# MCU.net
KiCad netlist of a schematic drawn in Altium Designer
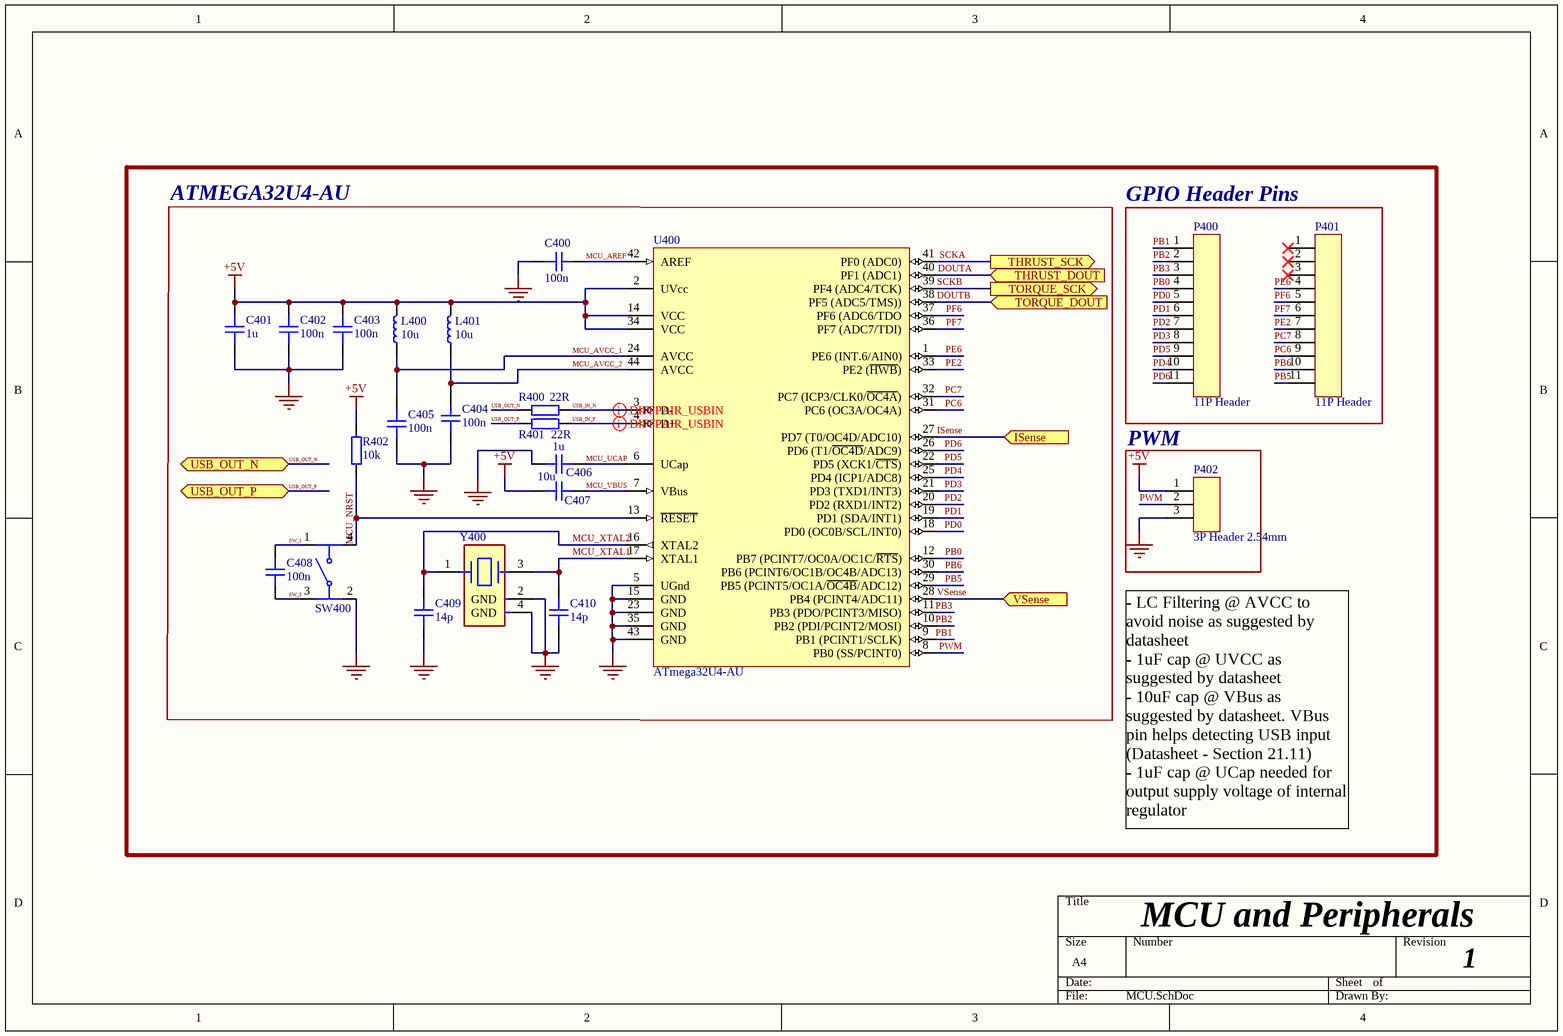
[diagram p0: MCU.SchDoc]

(export (version "E")
  (design (tool "Eeschema 10.0.6"))
  (components
    (comp (ref "C400")
      (value "100n")
      (footprint "CAP_0603")
      (description "Capacitor SMD 0603")
      (libsource (lib "Footprint-Lib-PhilsLab") (part "CAP_0603"))
    )
    (comp (ref "C401")
      (value "1u")
      (footprint "CAP_0603")
      (description "Capacitor SMD 0603")
      (libsource (lib "Footprint-Lib-PhilsLab") (part "CAP_0603"))
    )
    (comp (ref "C402")
      (value "100n")
      (footprint "CAP_0603")
      (description "Capacitor SMD 0603")
      (libsource (lib "Footprint-Lib-PhilsLab") (part "CAP_0603"))
    )
    (comp (ref "C403")
      (value "100n")
      (footprint "CAP_0603")
      (description "Capacitor SMD 0603")
      (libsource (lib "Footprint-Lib-PhilsLab") (part "CAP_0603"))
    )
    (comp (ref "C404")
      (value "100n")
      (footprint "CAP_0603")
      (description "Capacitor SMD 0603")
      (libsource (lib "Footprint-Lib-PhilsLab") (part "CAP_0603"))
    )
    (comp (ref "C405")
      (value "100n")
      (footprint "CAP_0603")
      (description "Capacitor SMD 0603")
      (libsource (lib "Footprint-Lib-PhilsLab") (part "CAP_0603"))
    )
    (comp (ref "C406")
      (value "1u")
      (footprint "CAP_0603")
      (description "Capacitor SMD 0603")
      (libsource (lib "Footprint-Lib-PhilsLab") (part "CAP_0603"))
    )
    (comp (ref "C407")
      (value "10u")
      (footprint "CAP_0603")
      (description "Capacitor SMD 0603")
      (libsource (lib "Footprint-Lib-PhilsLab") (part "CAP_0603"))
    )
    (comp (ref "C408")
      (value "100n")
      (footprint "CAP_0603")
      (description "Capacitor SMD 0603")
      (libsource (lib "Footprint-Lib-PhilsLab") (part "CAP_0603"))
    )
    (comp (ref "C409")
      (value "14p")
      (footprint "CAP_0603")
      (description "Capacitor SMD 0603")
      (libsource (lib "Footprint-Lib-PhilsLab") (part "CAP_0603"))
    )
    (comp (ref "C410")
      (value "14p")
      (footprint "CAP_0603")
      (description "Capacitor SMD 0603")
      (libsource (lib "Footprint-Lib-PhilsLab") (part "CAP_0603"))
    )
    (comp (ref "L400")
      (value "10u")
      (footprint "IND_0603")
      (description "Inductor SMD 0603")
      (libsource (lib "Footprint-Lib-PhilsLab") (part "IND_0603"))
    )
    (comp (ref "L401")
      (value "10u")
      (footprint "IND_0603")
      (description "Inductor SMD 0603")
      (libsource (lib "Footprint-Lib-PhilsLab") (part "IND_0603"))
    )
    (comp (ref "P400")
      (value "11P Header")
      (footprint "PZ254-1-11-Z-2.5-G1")
      (fields
        (field (name "MANUFACTURER") "HCTL")
        (field (name "MFR. PART NUMBER") "PZ254-1-11-Z-2.5-G1")
        (field (name "JLCPCB PART NUMBER") "C18197918")
      )
      (libsource (lib "Sidharth's Schematic Library") (part "PZ254-1-11-Z-2.5-G1"))
    )
    (comp (ref "P401")
      (value "11P Header")
      (footprint "PZ254-1-11-Z-2.5-G1")
      (fields
        (field (name "MANUFACTURER") "HCTL")
        (field (name "MFR. PART NUMBER") "PZ254-1-11-Z-2.5-G1")
        (field (name "JLCPCB PART NUMBER") "C18197918")
      )
      (libsource (lib "Sidharth's Schematic Library") (part "PZ254-1-11-Z-2.5-G1"))
    )
    (comp (ref "P402")
      (value "3P Header 2.54mm")
      (footprint "3P Header 2.54mm")
      (fields
        (field (name "MANUFACTURER") "XFCN")
        (field (name "MFR. PART #") "PZ254V-11-03P")
        (field (name "JLCPCB PART #") "C2937625")
      )
      (libsource (lib "Sidharth's Schematic Library") (part "PZ254V-11-03P"))
    )
    (comp (ref "R400")
      (value "22R")
      (footprint "RES_0603")
      (description "Resistor SMD 0603")
      (libsource (lib "Footprint-Lib-PhilsLab") (part "RES_0603"))
    )
    (comp (ref "R401")
      (value "22R")
      (footprint "RES_0603")
      (description "Resistor SMD 0603")
      (libsource (lib "Footprint-Lib-PhilsLab") (part "RES_0603"))
    )
    (comp (ref "R402")
      (value "10k")
      (footprint "RES_0603")
      (description "Resistor SMD 0603")
      (libsource (lib "Footprint-Lib-PhilsLab") (part "RES_0603"))
    )
    (comp (ref "SW400")
      (value "C318884")
      (footprint "C318884")
      (fields
        (field (name "MANUFACTURER") "XKB Connection")
        (field (name "MFR PART NUMBER") "TS-1187 A-B-A-B")
      )
      (libsource (lib "Sidharth's Schematic Library") (part "C318884"))
    )
    (comp (ref "U400")
      (value "ATmega32U4-AU")
      (footprint "44ML_M")
      (libsource (lib "Altium Content Vault") (part "MC-8B-ATM16U4-SQ44"))
    )
    (comp (ref "Y400")
      (value "7M-16.000MEEQ-T")
      (footprint "FP-7M-MFG")
      (description "Crystal 16MHz, 10ppm, 10pF, 60Ω")
      (fields (field (name "TOLERANCE") "10ppm"))
      (libsource (lib "Altium Content Vault") (part "41079aabb0e87794b56622915be14ed"))
    )
  )
  (nets
    (net (code "1") (name "+5V") (class "Default")
      (node (ref "C401") (pin "2") (pinfunction "2_2") (pintype "passive"))
      (node (ref "C402") (pin "2") (pinfunction "2_2") (pintype "passive"))
      (node (ref "C403") (pin "2") (pinfunction "2_2") (pintype "passive"))
      (node (ref "C407") (pin "2") (pinfunction "2_2") (pintype "passive"))
      (node (ref "L400") (pin "2") (pinfunction "2_2") (pintype "passive"))
      (node (ref "L401") (pin "2") (pinfunction "2_2") (pintype "passive"))
      (node (ref "P402") (pin "1") (pintype "passive"))
      (node (ref "R402") (pin "2") (pinfunction "2_2") (pintype "passive"))
      (node (ref "U400") (pin "14") (pinfunction "VCC_14") (pintype "power_in"))
      (node (ref "U400") (pin "2") (pinfunction "UVcc_2") (pintype "power_in"))
      (node (ref "U400") (pin "34") (pinfunction "VCC_34") (pintype "power_in"))
    )
    (net (code "2") (name "/DOUTA") (class "Default")
      (node (ref "U400") (pin "40") (pinfunction "PF1_(ADC1)_40") (pintype "bidirectional"))
    )
    (net (code "3") (name "/DOUTB") (class "Default")
      (node (ref "U400") (pin "38") (pinfunction "PF5_(ADC5/TMS))_38") (pintype "bidirectional"))
    )
    (net (code "4") (name "/ISense") (class "Default")
      (node (ref "U400") (pin "27") (pinfunction "PD7_(T0/OC4D/ADC10)_27") (pintype "bidirectional"))
    )
    (net (code "5") (name "/MCU_AREF") (class "Default")
      (node (ref "C400") (pin "1") (pinfunction "1_1") (pintype "passive"))
      (node (ref "U400") (pin "42") (pinfunction "AREF_42") (pintype "input"))
    )
    (net (code "6") (name "/MCU_AVCC_1") (class "Default")
      (node (ref "C405") (pin "2") (pinfunction "2_2") (pintype "passive"))
      (node (ref "L400") (pin "1") (pinfunction "1_1") (pintype "passive"))
      (node (ref "U400") (pin "24") (pinfunction "AVCC_24") (pintype "power_in"))
    )
    (net (code "7") (name "/MCU_AVCC_2") (class "Default")
      (node (ref "C404") (pin "2") (pinfunction "2_2") (pintype "passive"))
      (node (ref "L401") (pin "1") (pinfunction "1_1") (pintype "passive"))
      (node (ref "U400") (pin "44") (pinfunction "AVCC_44") (pintype "power_in"))
    )
    (net (code "8") (name "/MCU_NRST") (class "Default")
      (node (ref "R402") (pin "1") (pinfunction "1_1") (pintype "passive"))
      (node (ref "SW400") (pin "4") (pinfunction "4_4") (pintype "passive"))
      (node (ref "U400") (pin "13") (pinfunction "~{RESET}_13") (pintype "input"))
    )
    (net (code "9") (name "/MCU_UCAP") (class "Default")
      (node (ref "C406") (pin "1") (pinfunction "1_1") (pintype "passive"))
      (node (ref "U400") (pin "6") (pinfunction "UCap_6") (pintype "passive"))
    )
    (net (code "10") (name "/MCU_VBUS") (class "Default")
      (node (ref "C407") (pin "1") (pinfunction "1_1") (pintype "passive"))
      (node (ref "U400") (pin "7") (pinfunction "VBus_7") (pintype "input"))
    )
    (net (code "11") (name "/MCU_XTAL1") (class "Default")
      (node (ref "C410") (pin "2") (pinfunction "2_2") (pintype "passive"))
      (node (ref "U400") (pin "17") (pinfunction "XTAL1_17") (pintype "input"))
      (node (ref "Y400") (pin "3") (pinfunction "3_3") (pintype "passive"))
    )
    (net (code "12") (name "/MCU_XTAL2") (class "Default")
      (node (ref "C409") (pin "2") (pinfunction "2_2") (pintype "passive"))
      (node (ref "U400") (pin "16") (pinfunction "XTAL2_16") (pintype "output"))
      (node (ref "Y400") (pin "1") (pinfunction "1_1") (pintype "passive"))
    )
    (net (code "13") (name "/PB0") (class "Default")
      (node (ref "P400") (pin "4") (pintype "passive"))
      (node (ref "U400") (pin "12") (pinfunction "PB7_(PCINT7/OC0A/OC1C/~{RTS})_12") (pintype "bidirectional"))
    )
    (net (code "14") (name "/PB1") (class "Default")
      (node (ref "P400") (pin "1") (pintype "passive"))
      (node (ref "U400") (pin "9") (pinfunction "PB1_(PCINT1/SCLK)_9") (pintype "bidirectional"))
    )
    (net (code "15") (name "/PB2") (class "Default")
      (node (ref "P400") (pin "2") (pintype "passive"))
      (node (ref "U400") (pin "10") (pinfunction "PB2_(PDI/PCINT2/MOSI)_10") (pintype "bidirectional"))
    )
    (net (code "16") (name "/PB3") (class "Default")
      (node (ref "P400") (pin "3") (pintype "passive"))
      (node (ref "U400") (pin "11") (pinfunction "PB3_(PDO/PCINT3/MISO)_11") (pintype "bidirectional"))
    )
    (net (code "17") (name "/PB5") (class "Default")
      (node (ref "P401") (pin "11") (pintype "passive"))
      (node (ref "U400") (pin "29") (pinfunction "PB5_(PCINT5/OC1A/~{OC4B}/ADC12)_29") (pintype "bidirectional"))
    )
    (net (code "18") (name "/PB6") (class "Default")
      (node (ref "P401") (pin "10") (pintype "passive"))
      (node (ref "U400") (pin "30") (pinfunction "PB6_(PCINT6/OC1B/OC4B/ADC13)_30") (pintype "bidirectional"))
    )
    (net (code "19") (name "/PC6") (class "Default")
      (node (ref "P401") (pin "9") (pintype "passive"))
      (node (ref "U400") (pin "31") (pinfunction "PC6_(OC3A/OC4A)_31") (pintype "bidirectional"))
    )
    (net (code "20") (name "/PC7") (class "Default")
      (node (ref "P401") (pin "8") (pintype "passive"))
      (node (ref "U400") (pin "32") (pinfunction "PC7_(ICP3/CLK0/~{OC4A})_32") (pintype "bidirectional"))
    )
    (net (code "21") (name "/PD0") (class "Default")
      (node (ref "P400") (pin "5") (pintype "passive"))
      (node (ref "U400") (pin "18") (pinfunction "PD0_(OC0B/SCL/INT0)_18") (pintype "bidirectional"))
    )
    (net (code "22") (name "/PD1") (class "Default")
      (node (ref "P400") (pin "6") (pintype "passive"))
      (node (ref "U400") (pin "19") (pinfunction "PD1_(SDA/INT1)_19") (pintype "bidirectional"))
    )
    (net (code "23") (name "/PD2") (class "Default")
      (node (ref "P400") (pin "7") (pintype "passive"))
      (node (ref "U400") (pin "20") (pinfunction "PD2_(RXD1/INT2)_20") (pintype "bidirectional"))
    )
    (net (code "24") (name "/PD3") (class "Default")
      (node (ref "P400") (pin "8") (pintype "passive"))
      (node (ref "U400") (pin "21") (pinfunction "PD3_(TXD1/INT3)_21") (pintype "bidirectional"))
    )
    (net (code "25") (name "/PD4") (class "Default")
      (node (ref "P400") (pin "10") (pintype "passive"))
      (node (ref "U400") (pin "25") (pinfunction "PD4_(ICP1/ADC8)_25") (pintype "bidirectional"))
    )
    (net (code "26") (name "/PD5") (class "Default")
      (node (ref "P400") (pin "9") (pintype "passive"))
      (node (ref "U400") (pin "22") (pinfunction "PD5_(XCK1/~{CTS})_22") (pintype "bidirectional"))
    )
    (net (code "27") (name "/PD6") (class "Default")
      (node (ref "P400") (pin "11") (pintype "passive"))
      (node (ref "U400") (pin "26") (pinfunction "PD6_(T1/~{OC4D}/ADC9)_26") (pintype "bidirectional"))
    )
    (net (code "28") (name "/PE2") (class "Default")
      (node (ref "P401") (pin "7") (pintype "passive"))
      (node (ref "U400") (pin "33") (pinfunction "PE2_(~{HWB})_33") (pintype "bidirectional"))
    )
    (net (code "29") (name "/PE6") (class "Default")
      (node (ref "P401") (pin "4") (pintype "passive"))
      (node (ref "U400") (pin "1") (pinfunction "PE6_(INT.6/AIN0)_1") (pintype "bidirectional"))
    )
    (net (code "30") (name "/PF6") (class "Default")
      (node (ref "P401") (pin "5") (pintype "passive"))
      (node (ref "U400") (pin "37") (pinfunction "PF6_(ADC6/TDO_37") (pintype "bidirectional"))
    )
    (net (code "31") (name "/PF7") (class "Default")
      (node (ref "P401") (pin "6") (pintype "passive"))
      (node (ref "U400") (pin "36") (pinfunction "PF7_(ADC7/TDI)_36") (pintype "bidirectional"))
    )
    (net (code "32") (name "/PWM") (class "Default")
      (node (ref "P402") (pin "2") (pintype "passive"))
      (node (ref "U400") (pin "8") (pinfunction "PB0_(SS/PCINT0)_8") (pintype "bidirectional"))
    )
    (net (code "33") (name "/SCKA") (class "Default")
      (node (ref "U400") (pin "41") (pinfunction "PF0_(ADC0)_41") (pintype "bidirectional"))
    )
    (net (code "34") (name "/SCKB") (class "Default")
      (node (ref "U400") (pin "39") (pinfunction "PF4_(ADC4/TCK)_39") (pintype "bidirectional"))
    )
    (net (code "35") (name "/SW_1") (class "Default")
      (node (ref "C408") (pin "2") (pinfunction "2_2") (pintype "passive"))
      (node (ref "SW400") (pin "1") (pinfunction "1_1") (pintype "passive"))
    )
    (net (code "36") (name "/SW_3") (class "Default")
      (node (ref "C408") (pin "1") (pinfunction "1_1") (pintype "passive"))
      (node (ref "SW400") (pin "3") (pinfunction "3_3") (pintype "passive"))
    )
    (net (code "37") (name "/USB_IN_N") (class "Default")
      (node (ref "R400") (pin "2") (pinfunction "2_2") (pintype "passive"))
      (node (ref "U400") (pin "3") (pinfunction "D-_3") (pintype "bidirectional"))
    )
    (net (code "38") (name "/USB_IN_P") (class "Default")
      (node (ref "R401") (pin "2") (pinfunction "2_2") (pintype "passive"))
      (node (ref "U400") (pin "4") (pinfunction "D+_4") (pintype "bidirectional"))
    )
    (net (code "39") (name "/USB_OUT_N") (class "Default")
      (node (ref "R400") (pin "1") (pinfunction "1_1") (pintype "passive"))
    )
    (net (code "40") (name "/USB_OUT_P") (class "Default")
      (node (ref "R401") (pin "1") (pinfunction "1_1") (pintype "passive"))
    )
    (net (code "41") (name "/VSense") (class "Default")
      (node (ref "U400") (pin "28") (pinfunction "PB4_(PCINT4/ADC11)_28") (pintype "bidirectional"))
    )
    (net (code "42") (name "GND") (class "Default")
      (node (ref "C400") (pin "2") (pinfunction "2_2") (pintype "passive"))
      (node (ref "C401") (pin "1") (pinfunction "1_1") (pintype "passive"))
      (node (ref "C402") (pin "1") (pinfunction "1_1") (pintype "passive"))
      (node (ref "C403") (pin "1") (pinfunction "1_1") (pintype "passive"))
      (node (ref "C404") (pin "1") (pinfunction "1_1") (pintype "passive"))
      (node (ref "C405") (pin "1") (pinfunction "1_1") (pintype "passive"))
      (node (ref "C406") (pin "2") (pinfunction "2_2") (pintype "passive"))
      (node (ref "C409") (pin "1") (pinfunction "1_1") (pintype "passive"))
      (node (ref "C410") (pin "1") (pinfunction "1_1") (pintype "passive"))
      (node (ref "P402") (pin "3") (pintype "passive"))
      (node (ref "SW400") (pin "2") (pinfunction "2_2") (pintype "passive"))
      (node (ref "U400") (pin "15") (pinfunction "GND_15") (pintype "power_in"))
      (node (ref "U400") (pin "23") (pinfunction "GND_23") (pintype "power_in"))
      (node (ref "U400") (pin "35") (pinfunction "GND_35") (pintype "power_in"))
      (node (ref "U400") (pin "43") (pinfunction "GND_43") (pintype "power_in"))
      (node (ref "U400") (pin "5") (pinfunction "UGnd_5") (pintype "power_in"))
      (node (ref "Y400") (pin "2") (pinfunction "GND_2") (pintype "power_in"))
      (node (ref "Y400") (pin "4") (pinfunction "GND_4") (pintype "power_in"))
    )
    (net (code "43") (name "unconnected-(P401-Pad1)") (class "Default")
      (node (ref "P401") (pin "1") (pintype "passive+no_connect"))
    )
    (net (code "44") (name "unconnected-(P401-Pad2)") (class "Default")
      (node (ref "P401") (pin "2") (pintype "passive+no_connect"))
    )
    (net (code "45") (name "unconnected-(P401-Pad3)") (class "Default")
      (node (ref "P401") (pin "3") (pintype "passive+no_connect"))
    )
  )
)
